# BSB-to-UEXT.net
KiCad netlist of a schematic drawn in EAGLE
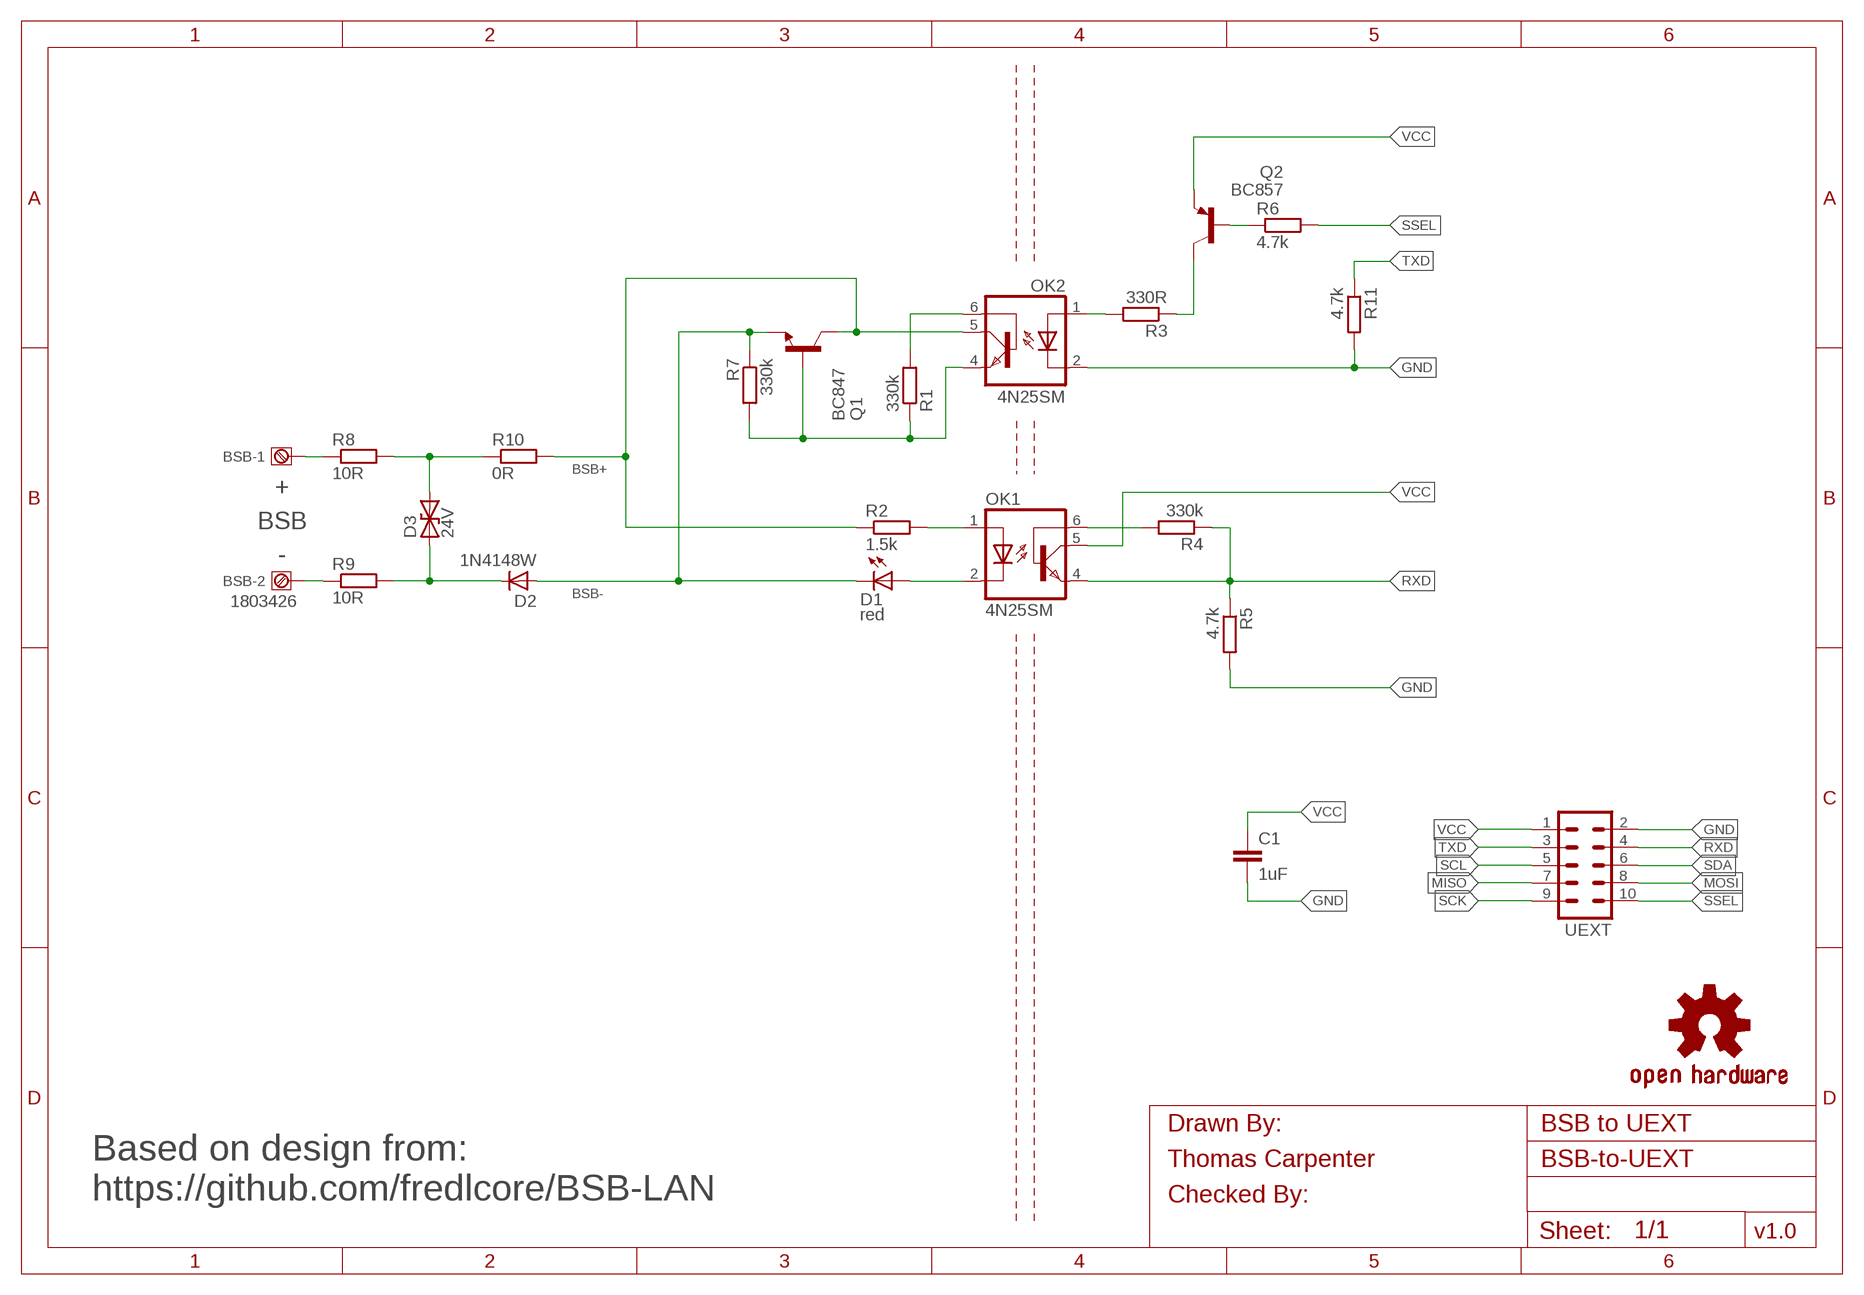
[diagram p0: schematic, sheet 1]

(export (version "E")
  (design (tool "Eeschema 10.0.6"))
  (components
    (comp (ref "BSB")
      (value "1803426")
      (footprint "eagle-import:1803426")
      (fields (field (name "LCSC_PART") "C480514") (field (name "LCSC_PART_1") "C480514"))
      (libsource (lib "eagle-import") (part "1803426"))
    )
    (comp (ref "C1")
      (value "1uF")
      (footprint "eagle-import:C0805")
      (fields (field (name "LCSC_PART") "C28323"))
      (libsource (lib "eagle-import") (part "C-EUC0805"))
    )
    (comp (ref "D1")
      (value "red")
      (footprint "eagle-import:CHIPLED_0805")
      (fields (field (name "LCSC_PART") "C84256"))
      (libsource (lib "eagle-import") (part "LEDCHIPLED_0805"))
    )
    (comp (ref "D2")
      (value "1N4148W")
      (footprint "eagle-import:SOD123")
      (fields (field (name "LCSC_PART") "C81598"))
      (libsource (lib "eagle-import") (part "DIODE-SOD123"))
    )
    (comp (ref "D3")
      (value "24V")
      (footprint "eagle-import:SMBG")
      (fields (field (name "LCSC_PART") "C83268"))
      (libsource (lib "eagle-import") (part "TVS-BIDIRSMB"))
    )
    (comp (ref "OK1")
      (value "4N25SM")
      (footprint "eagle-import:DIL6-SMD")
      (fields (field (name "LCSC_PART") "C258246") (field (name "LCSC_PART_1") "C258246"))
      (libsource (lib "eagle-import") (part "4N?MS25"))
    )
    (comp (ref "OK2")
      (value "4N25SM")
      (footprint "eagle-import:DIL6-SMD")
      (fields (field (name "LCSC_PART") "C258246") (field (name "LCSC_PART_1") "C258246"))
      (libsource (lib "eagle-import") (part "4N?MS25"))
    )
    (comp (ref "Q1")
      (value "BC847")
      (footprint "eagle-import:SOT23")
      (fields (field (name "LCSC_PART") "C130417") (field (name "LCSC_PART_1") "C130417"))
      (libsource (lib "eagle-import") (part "BC847"))
    )
    (comp (ref "Q2")
      (value "BC857")
      (footprint "eagle-import:SOT23-BEC")
      (fields (field (name "LCSC_PART") "C426782") (field (name "LCSC_PART_1") "C426782"))
      (libsource (lib "eagle-import") (part "BC857"))
    )
    (comp (ref "R1")
      (value "330k")
      (footprint "eagle-import:R0805")
      (fields (field (name "LCSC_PART") "C17629"))
      (libsource (lib "eagle-import") (part "R-EU_R0805"))
    )
    (comp (ref "R2")
      (value "1.5k")
      (footprint "eagle-import:R0805")
      (fields (field (name "LCSC_PART") "C4310"))
      (libsource (lib "eagle-import") (part "R-EU_R0805"))
    )
    (comp (ref "R3")
      (value "330R")
      (footprint "eagle-import:R0805")
      (fields (field (name "LCSC_PART") "C17630"))
      (libsource (lib "eagle-import") (part "R-EU_R0805"))
    )
    (comp (ref "R4")
      (value "330k")
      (footprint "eagle-import:R0805")
      (fields (field (name "LCSC_PART") "C17629"))
      (libsource (lib "eagle-import") (part "R-EU_R0805"))
    )
    (comp (ref "R5")
      (value "4.7k")
      (footprint "eagle-import:R0805")
      (fields (field (name "LCSC_PART") "C17673"))
      (libsource (lib "eagle-import") (part "R-EU_R0805"))
    )
    (comp (ref "R6")
      (value "4.7k")
      (footprint "eagle-import:R0805")
      (fields (field (name "LCSC_PART") "C17673"))
      (libsource (lib "eagle-import") (part "R-EU_R0805"))
    )
    (comp (ref "R7")
      (value "330k")
      (footprint "eagle-import:R0805")
      (fields (field (name "LCSC_PART") "C17629"))
      (libsource (lib "eagle-import") (part "R-EU_R0805"))
    )
    (comp (ref "R8")
      (value "10R")
      (footprint "eagle-import:R1206")
      (fields (field (name "LCSC_PART") "C17903"))
      (libsource (lib "eagle-import") (part "R-EU_R1206"))
    )
    (comp (ref "R9")
      (value "10R")
      (footprint "eagle-import:R1206")
      (fields (field (name "LCSC_PART") "C17903"))
      (libsource (lib "eagle-import") (part "R-EU_R1206"))
    )
    (comp (ref "R10")
      (value "0R")
      (footprint "eagle-import:R1206L")
      (fields (field (name "LCSC_PART") "C17888"))
      (libsource (lib "eagle-import") (part "R-EU_R1206L"))
    )
    (comp (ref "R11")
      (value "4.7k")
      (footprint "eagle-import:R0805")
      (fields (field (name "LCSC_PART") "C17673"))
      (libsource (lib "eagle-import") (part "R-EU_R0805"))
    )
    (comp (ref "U$3")
      (value "DNI")
      (footprint "eagle-import:OSHW-LOGO-M")
      (libsource (lib "eagle-import") (part "OSHW-LOGOM"))
    )
    (comp (ref "UEXT")
      (value "ML10F")
      (footprint "eagle-import:ML10F")
      (libsource (lib "eagle-import") (part "ML10F"))
    )
  )
  (nets
    (net (code "1") (name "/BSB+") (class "Default")
      (node (ref "OK2") (pin "5") (pinfunction "COL_5") (pintype "passive"))
      (node (ref "Q1") (pin "3") (pinfunction "C_3") (pintype "passive"))
      (node (ref "R10") (pin "2") (pinfunction "2_2") (pintype "passive"))
      (node (ref "R2") (pin "1") (pinfunction "1_1") (pintype "passive"))
    )
    (net (code "2") (name "/BSB-") (class "Default")
      (node (ref "D1") (pin "C") (pinfunction "C_C") (pintype "passive"))
      (node (ref "D2") (pin "A") (pinfunction "A_A") (pintype "passive"))
      (node (ref "Q1") (pin "2") (pinfunction "E_2") (pintype "passive"))
      (node (ref "R7") (pin "1") (pinfunction "1_1") (pintype "passive"))
    )
    (net (code "3") (name "GND") (class "Default")
      (node (ref "C1") (pin "2") (pinfunction "2_2") (pintype "passive"))
      (node (ref "OK2") (pin "2") (pinfunction "C_2") (pintype "passive"))
      (node (ref "R11") (pin "2") (pinfunction "2_2") (pintype "passive"))
      (node (ref "R5") (pin "2") (pinfunction "2_2") (pintype "passive"))
      (node (ref "UEXT") (pin "2") (pinfunction "2_2") (pintype "passive"))
    )
    (net (code "4") (name "MISO") (class "Default")
      (node (ref "UEXT") (pin "7") (pinfunction "7_7") (pintype "passive"))
    )
    (net (code "5") (name "MOSI") (class "Default")
      (node (ref "UEXT") (pin "8") (pinfunction "8_8") (pintype "passive"))
    )
    (net (code "6") (name "Net-(BSB-Pad1)") (class "Default")
      (node (ref "BSB") (pin "1") (pinfunction "1_1") (pintype "passive"))
      (node (ref "R8") (pin "1") (pinfunction "1_1") (pintype "passive"))
    )
    (net (code "7") (name "Net-(BSBB-1)") (class "Default")
      (node (ref "BSB") (pin "2") (pinfunction "1_2") (pintype "passive"))
      (node (ref "R9") (pin "1") (pinfunction "1_1") (pintype "passive"))
    )
    (net (code "8") (name "Net-(D2-PadC)") (class "Default")
      (node (ref "D2") (pin "C") (pinfunction "C_C") (pintype "passive"))
      (node (ref "D3") (pin "1") (pinfunction "1_1") (pintype "passive"))
      (node (ref "R9") (pin "2") (pinfunction "2_2") (pintype "passive"))
    )
    (net (code "9") (name "Net-(D3-Pad2)") (class "Default")
      (node (ref "D3") (pin "2") (pinfunction "2_2") (pintype "passive"))
      (node (ref "R10") (pin "1") (pinfunction "1_1") (pintype "passive"))
      (node (ref "R8") (pin "2") (pinfunction "2_2") (pintype "passive"))
    )
    (net (code "10") (name "Net-(OK1-A)") (class "Default")
      (node (ref "OK1") (pin "1") (pinfunction "A_1") (pintype "passive"))
      (node (ref "R2") (pin "2") (pinfunction "2_2") (pintype "passive"))
    )
    (net (code "11") (name "Net-(OK1-BAS)") (class "Default")
      (node (ref "OK1") (pin "6") (pinfunction "BAS_6") (pintype "passive"))
      (node (ref "R4") (pin "2") (pinfunction "2_2") (pintype "passive"))
    )
    (net (code "12") (name "Net-(OK1-C)") (class "Default")
      (node (ref "D1") (pin "A") (pinfunction "A_A") (pintype "passive"))
      (node (ref "OK1") (pin "2") (pinfunction "C_2") (pintype "passive"))
    )
    (net (code "13") (name "Net-(OK2-A)") (class "Default")
      (node (ref "OK2") (pin "1") (pinfunction "A_1") (pintype "passive"))
      (node (ref "R3") (pin "2") (pinfunction "2_2") (pintype "passive"))
    )
    (net (code "14") (name "Net-(OK2-BAS)") (class "Default")
      (node (ref "OK2") (pin "6") (pinfunction "BAS_6") (pintype "passive"))
      (node (ref "R1") (pin "2") (pinfunction "2_2") (pintype "passive"))
    )
    (net (code "15") (name "Net-(OK2-EMI)") (class "Default")
      (node (ref "OK2") (pin "4") (pinfunction "EMI_4") (pintype "passive"))
      (node (ref "Q1") (pin "1") (pinfunction "B_1") (pintype "passive"))
      (node (ref "R1") (pin "1") (pinfunction "1_1") (pintype "passive"))
      (node (ref "R7") (pin "2") (pinfunction "2_2") (pintype "passive"))
    )
    (net (code "16") (name "Net-(Q2-PadB)") (class "Default")
      (node (ref "Q2") (pin "B") (pinfunction "B_B") (pintype "passive"))
      (node (ref "R6") (pin "1") (pinfunction "1_1") (pintype "passive"))
    )
    (net (code "17") (name "Net-(Q2-PadC)") (class "Default")
      (node (ref "Q2") (pin "C") (pinfunction "C_C") (pintype "passive"))
      (node (ref "R3") (pin "1") (pinfunction "1_1") (pintype "passive"))
    )
    (net (code "18") (name "RXD") (class "Default")
      (node (ref "OK1") (pin "4") (pinfunction "EMI_4") (pintype "passive"))
      (node (ref "R4") (pin "1") (pinfunction "1_1") (pintype "passive"))
      (node (ref "R5") (pin "1") (pinfunction "1_1") (pintype "passive"))
      (node (ref "UEXT") (pin "4") (pinfunction "4_4") (pintype "passive"))
    )
    (net (code "19") (name "SCK") (class "Default")
      (node (ref "UEXT") (pin "9") (pinfunction "9_9") (pintype "passive"))
    )
    (net (code "20") (name "SCL") (class "Default")
      (node (ref "UEXT") (pin "5") (pinfunction "5_5") (pintype "passive"))
    )
    (net (code "21") (name "SDA") (class "Default")
      (node (ref "UEXT") (pin "6") (pinfunction "6_6") (pintype "passive"))
    )
    (net (code "22") (name "SSEL") (class "Default")
      (node (ref "R6") (pin "2") (pinfunction "2_2") (pintype "passive"))
      (node (ref "UEXT") (pin "10") (pinfunction "10_10") (pintype "passive"))
    )
    (net (code "23") (name "TXD") (class "Default")
      (node (ref "R11") (pin "1") (pinfunction "1_1") (pintype "passive"))
      (node (ref "UEXT") (pin "3") (pinfunction "3_3") (pintype "passive"))
    )
    (net (code "24") (name "VCC") (class "Default")
      (node (ref "C1") (pin "1") (pinfunction "1_1") (pintype "passive"))
      (node (ref "OK1") (pin "5") (pinfunction "COL_5") (pintype "passive"))
      (node (ref "Q2") (pin "E") (pinfunction "E_E") (pintype "passive"))
      (node (ref "UEXT") (pin "1") (pinfunction "1_1") (pintype "passive"))
    )
  )
)
